# HEATER.net
KiCad netlist of a schematic drawn in Altium Designer
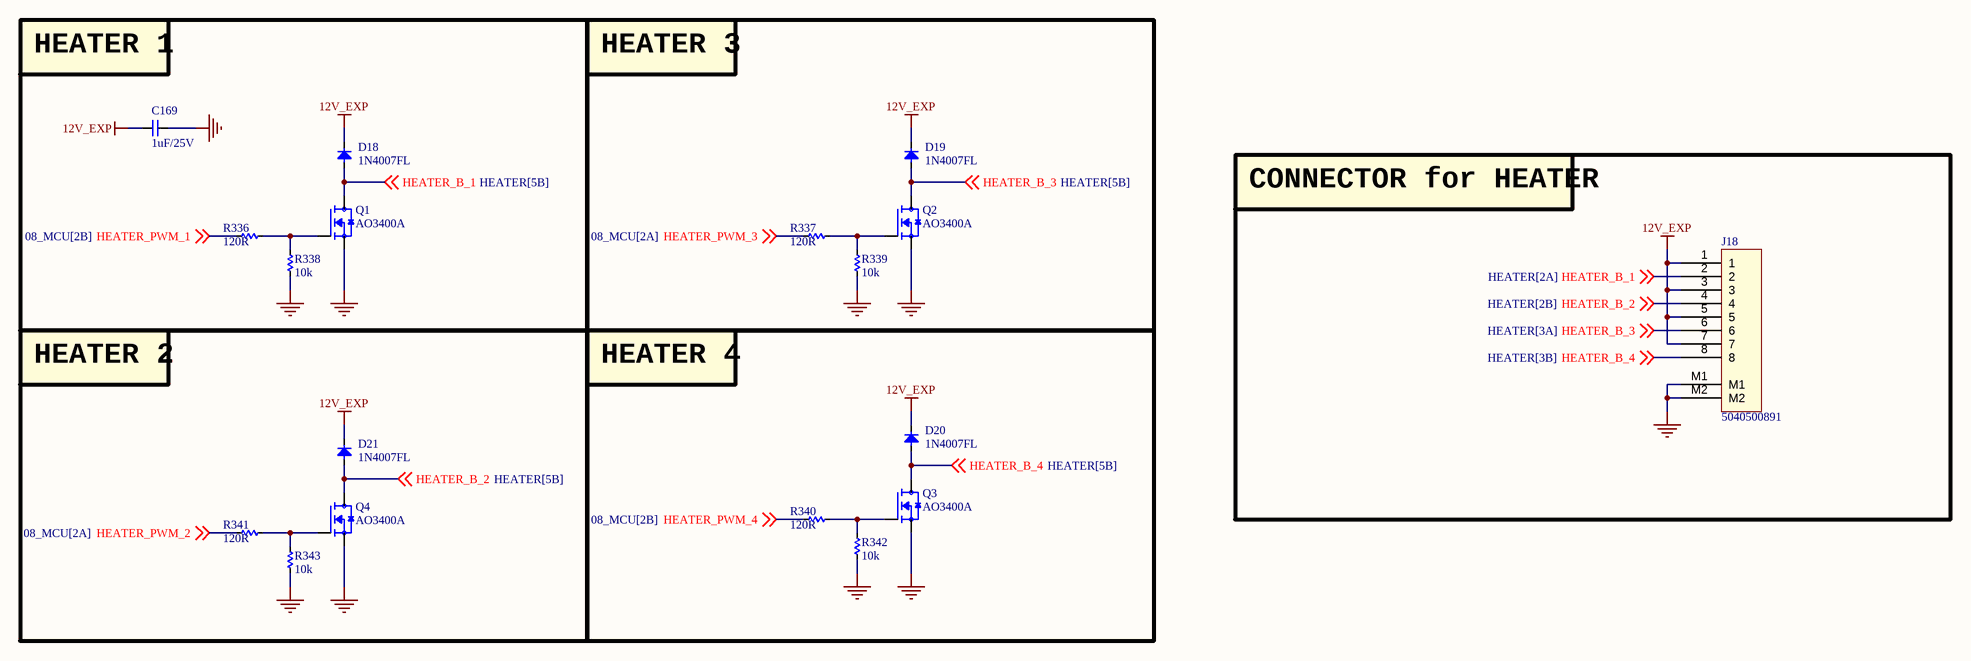
[diagram p0: HEATER.SchDoc]

(export (version "E")
  (design (tool "Eeschema 10.0.6"))
  (components
    (comp (ref "C169")
      (value "1uF/25V")
      (footprint "CAP_C_1005X60")
      (description "CAP")
      (libsource (lib "LABLIB") (part "_CAP_C_2"))
    )
    (comp (ref "D18")
      (value "1N4007FL")
      (footprint "SOD3717X145N")
      (description "Default Diode")
      (fields (field (name "PUBLISHER") "Altium Limited"))
      (libsource (lib "LABLIB") (part "Diode SMD"))
    )
    (comp (ref "D19")
      (value "1N4007FL")
      (footprint "SOD3717X145N")
      (description "Default Diode")
      (fields (field (name "PUBLISHER") "Altium Limited"))
      (libsource (lib "LABLIB") (part "Diode SMD"))
    )
    (comp (ref "D20")
      (value "1N4007FL")
      (footprint "SOD3717X145N")
      (description "Default Diode")
      (fields (field (name "PUBLISHER") "Altium Limited"))
      (libsource (lib "LABLIB") (part "Diode SMD"))
    )
    (comp (ref "D21")
      (value "1N4007FL")
      (footprint "SOD3717X145N")
      (description "Default Diode")
      (fields (field (name "PUBLISHER") "Altium Limited"))
      (libsource (lib "LABLIB") (part "Diode SMD"))
    )
    (comp (ref "J18")
      (value "5040500891")
      (footprint "MOLEX_5040500891")
      (libsource (lib "LABLIB") (part "Header 8x1_2M"))
    )
    (comp (ref "Q1")
      (value "AO3400A")
      (footprint "SOT95P240X120-3N")
      (description "N-Channel 30 V 5.7A (Ta) 1.4W (Ta) Surface Mount SOT-23-3")
      (fields (field (name "MF") "Alpha & Omega Semiconductor"))
      (libsource (lib "LABLIB") (part "MOSFET_N"))
    )
    (comp (ref "Q2")
      (value "AO3400A")
      (footprint "SOT95P240X120-3N")
      (description "N-Channel 30 V 5.7A (Ta) 1.4W (Ta) Surface Mount SOT-23-3")
      (fields (field (name "MF") "Alpha & Omega Semiconductor"))
      (libsource (lib "LABLIB") (part "MOSFET_N"))
    )
    (comp (ref "Q3")
      (value "AO3400A")
      (footprint "SOT95P240X120-3N")
      (description "N-Channel 30 V 5.7A (Ta) 1.4W (Ta) Surface Mount SOT-23-3")
      (fields (field (name "MF") "Alpha & Omega Semiconductor"))
      (libsource (lib "LABLIB") (part "MOSFET_N"))
    )
    (comp (ref "Q4")
      (value "AO3400A")
      (footprint "SOT95P240X120-3N")
      (description "N-Channel 30 V 5.7A (Ta) 1.4W (Ta) Surface Mount SOT-23-3")
      (fields (field (name "MF") "Alpha & Omega Semiconductor"))
      (libsource (lib "LABLIB") (part "MOSFET_N"))
    )
    (comp (ref "R336")
      (value "120R")
      (footprint "RES_C_1005X40")
      (description "RES")
      (libsource (lib "LABLIB") (part "_RES_B_2"))
    )
    (comp (ref "R337")
      (value "120R")
      (footprint "RES_C_1005X40")
      (description "RES")
      (libsource (lib "LABLIB") (part "_RES_B_2"))
    )
    (comp (ref "R338")
      (value "10k")
      (footprint "RES_C_1005X40")
      (description "RES")
      (libsource (lib "LABLIB") (part "_RES_B_2"))
    )
    (comp (ref "R339")
      (value "10k")
      (footprint "RES_C_1005X40")
      (description "RES")
      (libsource (lib "LABLIB") (part "_RES_B_2"))
    )
    (comp (ref "R340")
      (value "120R")
      (footprint "RES_C_1005X40")
      (description "RES")
      (libsource (lib "LABLIB") (part "_RES_B_2"))
    )
    (comp (ref "R341")
      (value "120R")
      (footprint "RES_C_1005X40")
      (description "RES")
      (libsource (lib "LABLIB") (part "_RES_B_2"))
    )
    (comp (ref "R342")
      (value "10k")
      (footprint "RES_C_1005X40")
      (description "RES")
      (libsource (lib "LABLIB") (part "_RES_B_2"))
    )
    (comp (ref "R343")
      (value "10k")
      (footprint "RES_C_1005X40")
      (description "RES")
      (libsource (lib "LABLIB") (part "_RES_B_2"))
    )
  )
  (nets
    (net (code "1") (name "12V_EXP") (class "Default")
      (node (ref "C169") (pin "2") (pinfunction "2_2") (pintype "passive"))
      (node (ref "D18") (pin "1") (pinfunction "K_1") (pintype "passive"))
      (node (ref "D19") (pin "1") (pinfunction "K_1") (pintype "passive"))
      (node (ref "D20") (pin "1") (pinfunction "K_1") (pintype "passive"))
      (node (ref "D21") (pin "1") (pinfunction "K_1") (pintype "passive"))
      (node (ref "J18") (pin "1") (pinfunction "1_1") (pintype "passive"))
      (node (ref "J18") (pin "3") (pinfunction "3_3") (pintype "passive"))
      (node (ref "J18") (pin "5") (pinfunction "5_5") (pintype "passive"))
      (node (ref "J18") (pin "7") (pinfunction "7_7") (pintype "passive"))
    )
    (net (code "2") (name "GND") (class "Default")
      (node (ref "C169") (pin "1") (pinfunction "1_1") (pintype "passive"))
      (node (ref "J18") (pin "M1") (pinfunction "M1_M1") (pintype "passive"))
      (node (ref "J18") (pin "M2") (pinfunction "M2_M2") (pintype "passive"))
      (node (ref "Q1") (pin "2") (pinfunction "S_2") (pintype "passive"))
      (node (ref "Q2") (pin "2") (pinfunction "S_2") (pintype "passive"))
      (node (ref "Q3") (pin "2") (pinfunction "S_2") (pintype "passive"))
      (node (ref "Q4") (pin "2") (pinfunction "S_2") (pintype "passive"))
      (node (ref "R338") (pin "1") (pinfunction "1_1") (pintype "passive"))
      (node (ref "R339") (pin "1") (pinfunction "1_1") (pintype "passive"))
      (node (ref "R342") (pin "1") (pinfunction "1_1") (pintype "passive"))
      (node (ref "R343") (pin "1") (pinfunction "1_1") (pintype "passive"))
    )
    (net (code "3") (name "HEATER_B_1") (class "Default")
      (node (ref "D18") (pin "2") (pinfunction "A_2") (pintype "passive"))
      (node (ref "J18") (pin "2") (pinfunction "2_2") (pintype "passive"))
      (node (ref "Q1") (pin "3") (pinfunction "D_3") (pintype "passive"))
    )
    (net (code "4") (name "HEATER_B_2") (class "Default")
      (node (ref "D21") (pin "2") (pinfunction "A_2") (pintype "passive"))
      (node (ref "J18") (pin "4") (pinfunction "4_4") (pintype "passive"))
      (node (ref "Q4") (pin "3") (pinfunction "D_3") (pintype "passive"))
    )
    (net (code "5") (name "HEATER_B_3") (class "Default")
      (node (ref "D19") (pin "2") (pinfunction "A_2") (pintype "passive"))
      (node (ref "J18") (pin "6") (pinfunction "6_6") (pintype "passive"))
      (node (ref "Q2") (pin "3") (pinfunction "D_3") (pintype "passive"))
    )
    (net (code "6") (name "HEATER_B_4") (class "Default")
      (node (ref "D20") (pin "2") (pinfunction "A_2") (pintype "passive"))
      (node (ref "J18") (pin "8") (pinfunction "8_8") (pintype "passive"))
      (node (ref "Q3") (pin "3") (pinfunction "D_3") (pintype "passive"))
    )
    (net (code "7") (name "HEATER_PWM_1") (class "Default")
      (node (ref "R336") (pin "1") (pinfunction "1_1") (pintype "passive"))
    )
    (net (code "8") (name "HEATER_PWM_2") (class "Default")
      (node (ref "R341") (pin "1") (pinfunction "1_1") (pintype "passive"))
    )
    (net (code "9") (name "HEATER_PWM_3") (class "Default")
      (node (ref "R337") (pin "1") (pinfunction "1_1") (pintype "passive"))
    )
    (net (code "10") (name "HEATER_PWM_4") (class "Default")
      (node (ref "R340") (pin "1") (pinfunction "1_1") (pintype "passive"))
    )
    (net (code "11") (name "Net-(Q1-G)") (class "Default")
      (node (ref "Q1") (pin "1") (pinfunction "G_1") (pintype "passive"))
      (node (ref "R336") (pin "2") (pinfunction "2_2") (pintype "passive"))
      (node (ref "R338") (pin "2") (pinfunction "2_2") (pintype "passive"))
    )
    (net (code "12") (name "Net-(Q2-G)") (class "Default")
      (node (ref "Q2") (pin "1") (pinfunction "G_1") (pintype "passive"))
      (node (ref "R337") (pin "2") (pinfunction "2_2") (pintype "passive"))
      (node (ref "R339") (pin "2") (pinfunction "2_2") (pintype "passive"))
    )
    (net (code "13") (name "Net-(Q3-G)") (class "Default")
      (node (ref "Q3") (pin "1") (pinfunction "G_1") (pintype "passive"))
      (node (ref "R340") (pin "2") (pinfunction "2_2") (pintype "passive"))
      (node (ref "R342") (pin "2") (pinfunction "2_2") (pintype "passive"))
    )
    (net (code "14") (name "Net-(Q4-G)") (class "Default")
      (node (ref "Q4") (pin "1") (pinfunction "G_1") (pintype "passive"))
      (node (ref "R341") (pin "2") (pinfunction "2_2") (pintype "passive"))
      (node (ref "R343") (pin "2") (pinfunction "2_2") (pintype "passive"))
    )
  )
)
